# untitled.net
KiCad netlist of a schematic drawn in EAGLE
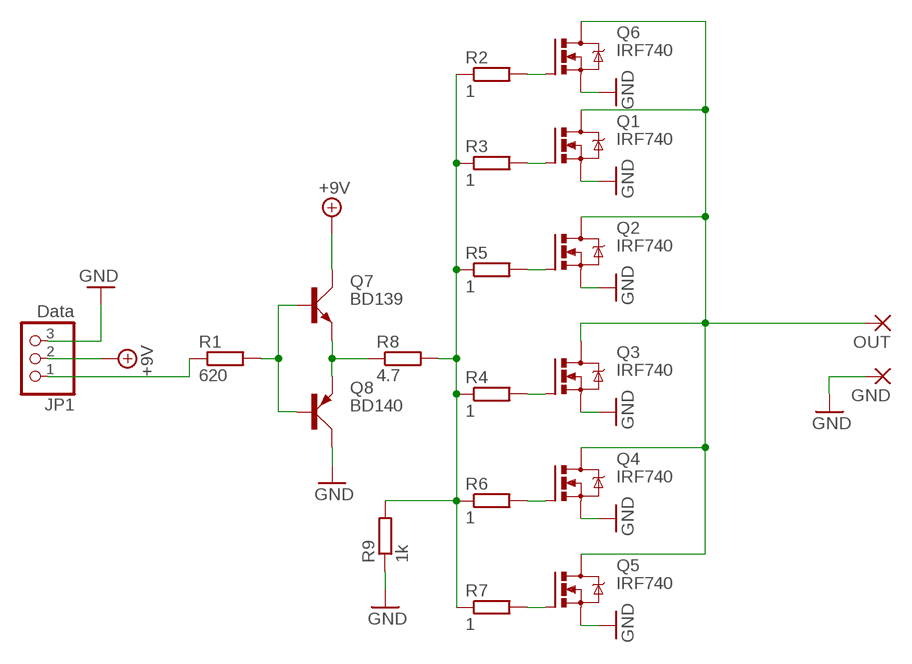
[diagram p0: schematic, sheet 1]

(export (version "E")
  (design (tool "Eeschema 10.0.6"))
  (components
    (comp (ref "GND")
      (value "WIREPADSMD5-2,5")
      (footprint "eagle-import:5-2,5")
      (libsource (lib "eagle-import") (part "WIREPADSMD5-2,5"))
    )
    (comp (ref "JP1")
      (value "Data")
      (footprint "eagle-import:1X03")
      (libsource (lib "eagle-import") (part "PINHD-1X3"))
    )
    (comp (ref "OUT")
      (value "WIREPADSMD5-2,5")
      (footprint "eagle-import:5-2,5")
      (libsource (lib "eagle-import") (part "WIREPADSMD5-2,5"))
    )
    (comp (ref "Q1")
      (value "IRF740")
      (footprint "eagle-import:TO220BV")
      (libsource (lib "eagle-import") (part "IRF740"))
    )
    (comp (ref "Q2")
      (value "IRF740")
      (footprint "eagle-import:TO220BV")
      (libsource (lib "eagle-import") (part "IRF740"))
    )
    (comp (ref "Q3")
      (value "IRF740")
      (footprint "eagle-import:TO220BV")
      (libsource (lib "eagle-import") (part "IRF740"))
    )
    (comp (ref "Q4")
      (value "IRF740")
      (footprint "eagle-import:TO220BV")
      (libsource (lib "eagle-import") (part "IRF740"))
    )
    (comp (ref "Q5")
      (value "IRF740")
      (footprint "eagle-import:TO220BV")
      (libsource (lib "eagle-import") (part "IRF740"))
    )
    (comp (ref "Q6")
      (value "IRF740")
      (footprint "eagle-import:TO220BV")
      (libsource (lib "eagle-import") (part "IRF740"))
    )
    (comp (ref "Q7")
      (value "BD139")
      (footprint "eagle-import:TO126AV")
      (libsource (lib "eagle-import") (part "BD139"))
    )
    (comp (ref "Q8")
      (value "BD140")
      (footprint "eagle-import:TO126AV")
      (libsource (lib "eagle-import") (part "BD140"))
    )
    (comp (ref "R1")
      (value "620")
      (footprint "eagle-import:R0805")
      (libsource (lib "eagle-import") (part "resistor_R-EU_R0805"))
    )
    (comp (ref "R2")
      (value "1")
      (footprint "eagle-import:R0805")
      (libsource (lib "eagle-import") (part "R-EU_R0805"))
    )
    (comp (ref "R3")
      (value "1")
      (footprint "eagle-import:R0805")
      (libsource (lib "eagle-import") (part "R-EU_R0805"))
    )
    (comp (ref "R4")
      (value "1")
      (footprint "eagle-import:R0805")
      (libsource (lib "eagle-import") (part "R-EU_R0805"))
    )
    (comp (ref "R5")
      (value "1")
      (footprint "eagle-import:R0805")
      (libsource (lib "eagle-import") (part "R-EU_R0805"))
    )
    (comp (ref "R6")
      (value "1")
      (footprint "eagle-import:R0805")
      (libsource (lib "eagle-import") (part "R-EU_R0805"))
    )
    (comp (ref "R7")
      (value "1")
      (footprint "eagle-import:R0805")
      (libsource (lib "eagle-import") (part "R-EU_R0805"))
    )
    (comp (ref "R8")
      (value "4.7")
      (footprint "eagle-import:R0805")
      (libsource (lib "eagle-import") (part "R-EU_R0805"))
    )
    (comp (ref "R9")
      (value "1k")
      (footprint "eagle-import:R0805")
      (libsource (lib "eagle-import") (part "resistor_R-EU_R0805"))
    )
  )
  (nets
    (net (code "1") (name "+9V") (class "Default")
      (node (ref "JP1") (pin "2") (pinfunction "2_2") (pintype "passive"))
      (node (ref "Q7") (pin "C") (pinfunction "C_C") (pintype "passive"))
    )
    (net (code "2") (name "GND") (class "Default")
      (node (ref "GND") (pin "1") (pinfunction "P_1") (pintype "passive"))
      (node (ref "JP1") (pin "3") (pinfunction "3_3") (pintype "passive"))
      (node (ref "Q1") (pin "S") (pinfunction "S_S") (pintype "passive"))
      (node (ref "Q2") (pin "S") (pinfunction "S_S") (pintype "passive"))
      (node (ref "Q3") (pin "S") (pinfunction "S_S") (pintype "passive"))
      (node (ref "Q4") (pin "S") (pinfunction "S_S") (pintype "passive"))
      (node (ref "Q5") (pin "S") (pinfunction "S_S") (pintype "passive"))
      (node (ref "Q6") (pin "S") (pinfunction "S_S") (pintype "passive"))
      (node (ref "Q8") (pin "C") (pinfunction "C_C") (pintype "passive"))
      (node (ref "R9") (pin "1") (pinfunction "1_1") (pintype "passive"))
    )
    (net (code "3") (name "Net-(JP1-Pad1)") (class "Default")
      (node (ref "JP1") (pin "1") (pinfunction "1_1") (pintype "passive"))
      (node (ref "R1") (pin "1") (pinfunction "1_1") (pintype "passive"))
    )
    (net (code "4") (name "Net-(OUT-P)") (class "Default")
      (node (ref "OUT") (pin "1") (pinfunction "P_1") (pintype "passive"))
      (node (ref "Q1") (pin "D") (pinfunction "D_D") (pintype "passive"))
      (node (ref "Q2") (pin "D") (pinfunction "D_D") (pintype "passive"))
      (node (ref "Q3") (pin "D") (pinfunction "D_D") (pintype "passive"))
      (node (ref "Q4") (pin "D") (pinfunction "D_D") (pintype "passive"))
      (node (ref "Q5") (pin "D") (pinfunction "D_D") (pintype "passive"))
      (node (ref "Q6") (pin "D") (pinfunction "D_D") (pintype "passive"))
    )
    (net (code "5") (name "Net-(Q1-PadG)") (class "Default")
      (node (ref "Q1") (pin "G") (pinfunction "G_G") (pintype "passive"))
      (node (ref "R3") (pin "2") (pinfunction "2_2") (pintype "passive"))
    )
    (net (code "6") (name "Net-(Q2-PadG)") (class "Default")
      (node (ref "Q2") (pin "G") (pinfunction "G_G") (pintype "passive"))
      (node (ref "R5") (pin "2") (pinfunction "2_2") (pintype "passive"))
    )
    (net (code "7") (name "Net-(Q3-PadG)") (class "Default")
      (node (ref "Q3") (pin "G") (pinfunction "G_G") (pintype "passive"))
      (node (ref "R4") (pin "2") (pinfunction "2_2") (pintype "passive"))
    )
    (net (code "8") (name "Net-(Q4-PadG)") (class "Default")
      (node (ref "Q4") (pin "G") (pinfunction "G_G") (pintype "passive"))
      (node (ref "R6") (pin "2") (pinfunction "2_2") (pintype "passive"))
    )
    (net (code "9") (name "Net-(Q5-PadG)") (class "Default")
      (node (ref "Q5") (pin "G") (pinfunction "G_G") (pintype "passive"))
      (node (ref "R7") (pin "2") (pinfunction "2_2") (pintype "passive"))
    )
    (net (code "10") (name "Net-(Q6-PadG)") (class "Default")
      (node (ref "Q6") (pin "G") (pinfunction "G_G") (pintype "passive"))
      (node (ref "R2") (pin "2") (pinfunction "2_2") (pintype "passive"))
    )
    (net (code "11") (name "Net-(Q7-PadB)") (class "Default")
      (node (ref "Q7") (pin "B") (pinfunction "B_B") (pintype "passive"))
      (node (ref "Q8") (pin "B") (pinfunction "B_B") (pintype "passive"))
      (node (ref "R1") (pin "2") (pinfunction "2_2") (pintype "passive"))
    )
    (net (code "12") (name "Net-(Q7-PadE)") (class "Default")
      (node (ref "Q7") (pin "E") (pinfunction "E_E") (pintype "passive"))
      (node (ref "Q8") (pin "E") (pinfunction "E_E") (pintype "passive"))
      (node (ref "R8") (pin "1") (pinfunction "1_1") (pintype "passive"))
    )
    (net (code "13") (name "Net-(R2-Pad1)") (class "Default")
      (node (ref "R2") (pin "1") (pinfunction "1_1") (pintype "passive"))
      (node (ref "R3") (pin "1") (pinfunction "1_1") (pintype "passive"))
      (node (ref "R4") (pin "1") (pinfunction "1_1") (pintype "passive"))
      (node (ref "R5") (pin "1") (pinfunction "1_1") (pintype "passive"))
      (node (ref "R6") (pin "1") (pinfunction "1_1") (pintype "passive"))
      (node (ref "R7") (pin "1") (pinfunction "1_1") (pintype "passive"))
      (node (ref "R8") (pin "2") (pinfunction "2_2") (pintype "passive"))
      (node (ref "R9") (pin "2") (pinfunction "2_2") (pintype "passive"))
    )
  )
)
